# HA_Ard.net
KiCad netlist of a schematic drawn in Altium Designer
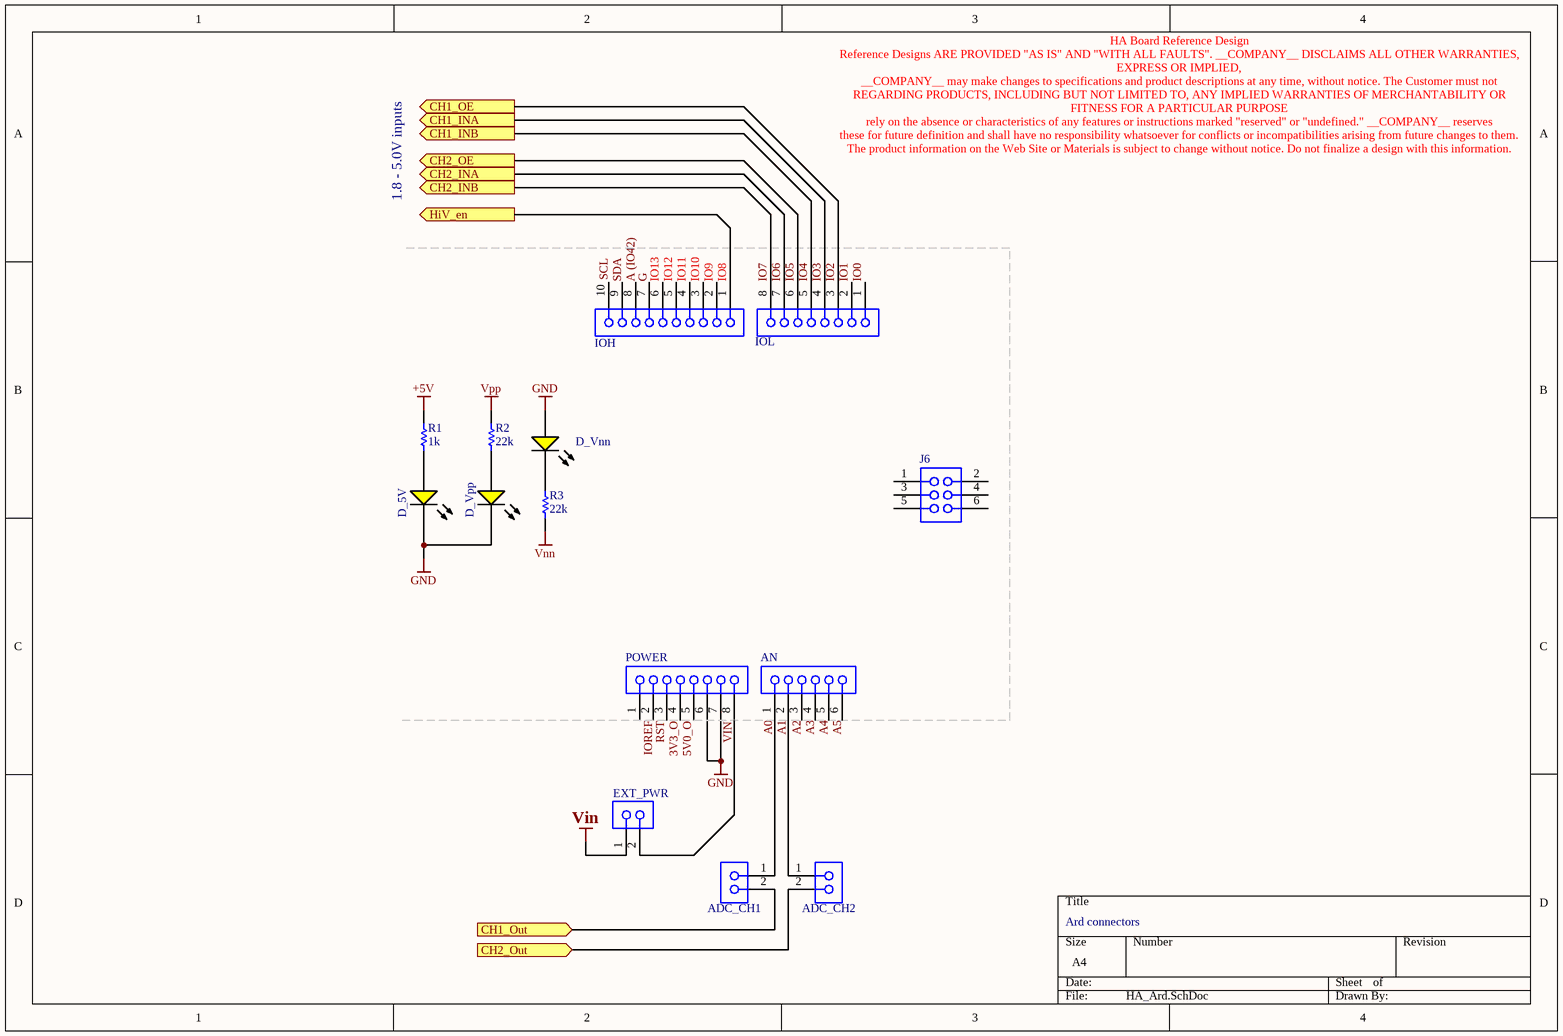
[diagram p0: HA_Ard.SchDoc]

(export (version "E")
  (design (tool "Eeschema 10.0.6"))
  (components
    (comp (ref "ADC_CH1")
      (value "PHF-102-03-L-S")
      (footprint "SMTC-PHF-102-03-X-S")
      (description "Press Fit Socket, Through-hole, Vertical, -55 to 125 degC, 2.54 mm Pitch, 2-Pin, Female, RoHS")
      (fields (field (name "MANUFACTURER") "Samtec"))
      (libsource (lib "") (part "CMP-1023-00105-1_1"))
    )
    (comp (ref "ADC_CH2")
      (value "PHF-102-03-L-S")
      (footprint "SMTC-PHF-102-03-X-S")
      (description "Press Fit Socket, Through-hole, Vertical, -55 to 125 degC, 2.54 mm Pitch, 2-Pin, Female, RoHS")
      (fields (field (name "MANUFACTURER") "Samtec"))
      (libsource (lib "Altium Content Vault") (part "CMP-1023-00105-1"))
    )
    (comp (ref "AN")
      (value "SSW-106-02-G-S")
      (footprint "SMTC-SSW-106-02-X-S")
      (description "SQ Post Socket, Through-hole, Vertical, -55 to 125 degC, 2.54mm Pitch, 6-Pin, Female, RoHS")
      (fields (field (name "MANUFACTURER") "Samtec"))
      (libsource (lib "Altium Content Vault") (part "CMP-1023-00359-1"))
    )
    (comp (ref "D_5V")
      (value "LED 0603 Green")
      (footprint "LTST-C190KSKT_V")
      (fields (field (name "MANUFACTURER") "Vishay") (field (name "MPN") "TLMG1100-GS08"))
      (libsource (lib "Altium Content Vault") (part "CMP-1674-00009-1"))
    )
    (comp (ref "D_Vnn")
      (value "LED 0603 Green")
      (footprint "LTST-C190KSKT_V")
      (fields (field (name "MANUFACTURER") "Vishay") (field (name "MPN") "TLMG1100-GS08"))
      (libsource (lib "Altium Content Vault") (part "CMP-1674-00009-1"))
    )
    (comp (ref "D_Vpp")
      (value "LED 0603 Green")
      (footprint "LTST-C190KSKT_V")
      (fields (field (name "MPN") "TLMG1100-GS08"))
      (libsource (lib "Altium Content Vault") (part "CMP-1674-00009-1"))
    )
    (comp (ref "EXT_PWR")
      (value "PHF-102-03-L-S")
      (footprint "SMTC-PHF-102-03-X-S")
      (description "Press Fit Socket, Through-hole, Vertical, -55 to 125 degC, 2.54 mm Pitch, 2-Pin, Female, RoHS")
      (fields (field (name "MANUFACTURER") "Samtec"))
      (libsource (lib "") (part "CMP-1023-00105-1_2"))
    )
    (comp (ref "IOH")
      (value "SSW-110-03-G-S")
      (footprint "SMTC-SSW-110-03-X-S")
      (description "SQ Post Socket, Through-hole, Vertical, -55 to 125 degC, 2.54 mm Pitch, 10-Pin, Female, RoHS")
      (fields (field (name "MANUFACTURER") "Samtec"))
      (libsource (lib "Altium Content Vault") (part "CMP-1023-00394-1"))
    )
    (comp (ref "IOL")
      (value "SSQ-108-01-F-S")
      (footprint "SMTC-SSQ-108-01-X-S")
      (description "SQ Post Socket, Through-hole, Vertical, -55 to 125 degC, 2.54 mm Pitch, 8-Pin, Female, RoHS")
      (fields (field (name "MANUFACTURER") "Samtec"))
      (libsource (lib "Altium Content Vault") (part "CMP-1023-00294-1"))
    )
    (comp (ref "J6")
      (value "SSW-103-01-F-D")
      (footprint "SMTC-SSW-103-01-X-D")
      (description "SQ Post Socket, Through-hole, Vertical, -55 to 125 degC, 2.54 mm Pitch, 6-Pin, Female, RoHS")
      (fields (field (name "MANUFACTURER") "Samtec"))
      (libsource (lib "Altium Content Vault") (part "CMP-1023-00329-1"))
    )
    (comp (ref "POWER")
      (value "SSQ-108-01-F-S")
      (footprint "SMTC-SSQ-108-01-X-S")
      (description "SQ Post Socket, Through-hole, Vertical, -55 to 125 degC, 2.54 mm Pitch, 8-Pin, Female, RoHS")
      (fields (field (name "MANUFACTURER") "Samtec"))
      (libsource (lib "Altium Content Vault") (part "CMP-1023-00294-1"))
    )
    (comp (ref "R1")
      (value "1k")
      (footprint "RESC0603(1608)_N")
      (fields (field (name "TOLERANCE") "1 %"))
      (libsource (lib "Altium Content Vault") (part "CMP-1012-00122-1"))
    )
    (comp (ref "R2")
      (value "22k")
      (footprint "RESC0603(1608)_N")
      (description "1% 0603 SMD")
      (fields (field (name "TOLERANCE") "1 %"))
      (libsource (lib "Altium Content Vault") (part "CMP-1012-00122-1"))
    )
    (comp (ref "R3")
      (value "22k")
      (footprint "RESC0603(1608)_N")
      (description "1% 0603 SMD")
      (fields (field (name "TOLERANCE") "1 %"))
      (libsource (lib "Altium Content Vault") (part "CMP-1012-00122-1"))
    )
  )
  (nets
    (net (code "1") (name "+5V") (class "Default")
      (node (ref "R1") (pin "1") (pinfunction "1_1") (pintype "passive"))
    )
    (net (code "11") (name "/CH1_Out") (class "Default")
      (node (ref "ADC_CH1") (pin "2") (pinfunction "2_2") (pintype "passive"))
    )
    (net (code "12") (name "/CH2_Out") (class "Default")
      (node (ref "ADC_CH2") (pin "2") (pinfunction "2_2") (pintype "passive"))
    )
    (net (code "14") (name "/HiV_en") (class "Default")
      (node (ref "IOH") (pin "1") (pinfunction "1_1") (pintype "passive"))
    )
    (net (code "15") (name "/IO0") (class "Default")
      (node (ref "IOL") (pin "1") (pinfunction "1_1") (pintype "passive"))
    )
    (net (code "16") (name "/IO1") (class "Default")
      (node (ref "IOL") (pin "2") (pinfunction "2_2") (pintype "passive"))
    )
    (net (code "17") (name "/IO2") (class "Default")
      (node (ref "IOL") (pin "3") (pinfunction "3_3") (pintype "passive"))
    )
    (net (code "18") (name "/IO3") (class "Default")
      (node (ref "IOL") (pin "4") (pinfunction "4_4") (pintype "passive"))
    )
    (net (code "19") (name "/IO4") (class "Default")
      (node (ref "IOL") (pin "5") (pinfunction "5_5") (pintype "passive"))
    )
    (net (code "20") (name "/IO5") (class "Default")
      (node (ref "IOL") (pin "6") (pinfunction "6_6") (pintype "passive"))
    )
    (net (code "21") (name "/IO6") (class "Default")
      (node (ref "IOL") (pin "7") (pinfunction "7_7") (pintype "passive"))
    )
    (net (code "22") (name "/IO7") (class "Default")
      (node (ref "IOL") (pin "8") (pinfunction "8_8") (pintype "passive"))
    )
    (net (code "28") (name "GND") (class "Default")
      (node (ref "D_5V") (pin "2") (pinfunction "K_2") (pintype "passive"))
      (node (ref "D_Vnn") (pin "1") (pinfunction "A_1") (pintype "passive"))
      (node (ref "D_Vpp") (pin "2") (pinfunction "K_2") (pintype "passive"))
      (node (ref "POWER") (pin "6") (pinfunction "6_6") (pintype "passive"))
      (node (ref "POWER") (pin "7") (pinfunction "7_7") (pintype "passive"))
    )
    (net (code "29") (name "Net-(ADC_CH1-Pad1)") (class "Default")
      (node (ref "ADC_CH1") (pin "1") (pinfunction "1_1") (pintype "passive"))
      (node (ref "AN") (pin "1") (pinfunction "1_1") (pintype "passive"))
    )
    (net (code "30") (name "Net-(ADC_CH2-Pad1)") (class "Default")
      (node (ref "ADC_CH2") (pin "1") (pinfunction "1_1") (pintype "passive"))
      (node (ref "AN") (pin "2") (pinfunction "2_2") (pintype "passive"))
    )
    (net (code "31") (name "Net-(D_5V-A)") (class "Default")
      (node (ref "D_5V") (pin "1") (pinfunction "A_1") (pintype "passive"))
      (node (ref "R1") (pin "2") (pinfunction "2_2") (pintype "passive"))
    )
    (net (code "32") (name "Net-(D_Vnn-K)") (class "Default")
      (node (ref "D_Vnn") (pin "2") (pinfunction "K_2") (pintype "passive"))
      (node (ref "R3") (pin "2") (pinfunction "2_2") (pintype "passive"))
    )
    (net (code "33") (name "Net-(D_Vpp-A)") (class "Default")
      (node (ref "D_Vpp") (pin "1") (pinfunction "A_1") (pintype "passive"))
      (node (ref "R2") (pin "2") (pinfunction "2_2") (pintype "passive"))
    )
    (net (code "34") (name "Net-(EXT_PWR-Pad2)") (class "Default")
      (node (ref "EXT_PWR") (pin "2") (pinfunction "2_2") (pintype "passive"))
      (node (ref "POWER") (pin "8") (pinfunction "8_8") (pintype "passive"))
    )
    (net (code "35") (name "Vin") (class "Default")
      (node (ref "EXT_PWR") (pin "1") (pinfunction "1_1") (pintype "passive"))
    )
    (net (code "36") (name "Vnn") (class "Default")
      (node (ref "R3") (pin "1") (pinfunction "1_1") (pintype "passive"))
    )
    (net (code "37") (name "Vpp") (class "Default")
      (node (ref "R2") (pin "1") (pinfunction "1_1") (pintype "passive"))
    )
    (net (code "38") (name "unconnected-(AN-Pad3)") (class "Default")
      (node (ref "AN") (pin "3") (pinfunction "3_3") (pintype "passive"))
    )
    (net (code "39") (name "unconnected-(AN-Pad4)") (class "Default")
      (node (ref "AN") (pin "4") (pinfunction "4_4") (pintype "passive"))
    )
    (net (code "40") (name "unconnected-(AN-Pad5)") (class "Default")
      (node (ref "AN") (pin "5") (pinfunction "5_5") (pintype "passive"))
    )
    (net (code "41") (name "unconnected-(AN-Pad6)") (class "Default")
      (node (ref "AN") (pin "6") (pinfunction "6_6") (pintype "passive"))
    )
    (net (code "42") (name "unconnected-(IOH-Pad2)") (class "Default")
      (node (ref "IOH") (pin "2") (pinfunction "2_2") (pintype "passive"))
    )
    (net (code "43") (name "unconnected-(IOH-Pad3)") (class "Default")
      (node (ref "IOH") (pin "3") (pinfunction "3_3") (pintype "passive"))
    )
    (net (code "44") (name "unconnected-(IOH-Pad4)") (class "Default")
      (node (ref "IOH") (pin "4") (pinfunction "4_4") (pintype "passive"))
    )
    (net (code "45") (name "unconnected-(IOH-Pad5)") (class "Default")
      (node (ref "IOH") (pin "5") (pinfunction "5_5") (pintype "passive"))
    )
    (net (code "46") (name "unconnected-(IOH-Pad6)") (class "Default")
      (node (ref "IOH") (pin "6") (pinfunction "6_6") (pintype "passive"))
    )
    (net (code "47") (name "unconnected-(IOH-Pad7)") (class "Default")
      (node (ref "IOH") (pin "7") (pinfunction "7_7") (pintype "passive"))
    )
    (net (code "48") (name "unconnected-(IOH-Pad8)") (class "Default")
      (node (ref "IOH") (pin "8") (pinfunction "8_8") (pintype "passive"))
    )
    (net (code "49") (name "unconnected-(IOH-Pad9)") (class "Default")
      (node (ref "IOH") (pin "9") (pinfunction "9_9") (pintype "passive"))
    )
    (net (code "50") (name "unconnected-(IOH-Pad10)") (class "Default")
      (node (ref "IOH") (pin "10") (pinfunction "10_10") (pintype "passive"))
    )
    (net (code "51") (name "unconnected-(J6-Pad1)") (class "Default")
      (node (ref "J6") (pin "1") (pinfunction "1_1") (pintype "passive"))
    )
    (net (code "52") (name "unconnected-(J6-Pad2)") (class "Default")
      (node (ref "J6") (pin "2") (pinfunction "2_2") (pintype "passive"))
    )
    (net (code "53") (name "unconnected-(J6-Pad3)") (class "Default")
      (node (ref "J6") (pin "3") (pinfunction "3_3") (pintype "passive"))
    )
    (net (code "54") (name "unconnected-(J6-Pad4)") (class "Default")
      (node (ref "J6") (pin "4") (pinfunction "4_4") (pintype "passive"))
    )
    (net (code "55") (name "unconnected-(J6-Pad5)") (class "Default")
      (node (ref "J6") (pin "5") (pinfunction "5_5") (pintype "passive"))
    )
    (net (code "56") (name "unconnected-(J6-Pad6)") (class "Default")
      (node (ref "J6") (pin "6") (pinfunction "6_6") (pintype "passive"))
    )
    (net (code "57") (name "unconnected-(POWER-Pad1)") (class "Default")
      (node (ref "POWER") (pin "1") (pinfunction "1_1") (pintype "passive"))
    )
    (net (code "58") (name "unconnected-(POWER-Pad2)") (class "Default")
      (node (ref "POWER") (pin "2") (pinfunction "2_2") (pintype "passive"))
    )
    (net (code "59") (name "unconnected-(POWER-Pad3)") (class "Default")
      (node (ref "POWER") (pin "3") (pinfunction "3_3") (pintype "passive"))
    )
    (net (code "60") (name "unconnected-(POWER-Pad4)") (class "Default")
      (node (ref "POWER") (pin "4") (pinfunction "4_4") (pintype "passive"))
    )
    (net (code "61") (name "unconnected-(POWER-Pad5)") (class "Default")
      (node (ref "POWER") (pin "5") (pinfunction "5_5") (pintype "passive"))
    )
  )
)
